# main.net
KiCad netlist of a schematic drawn in EAGLE
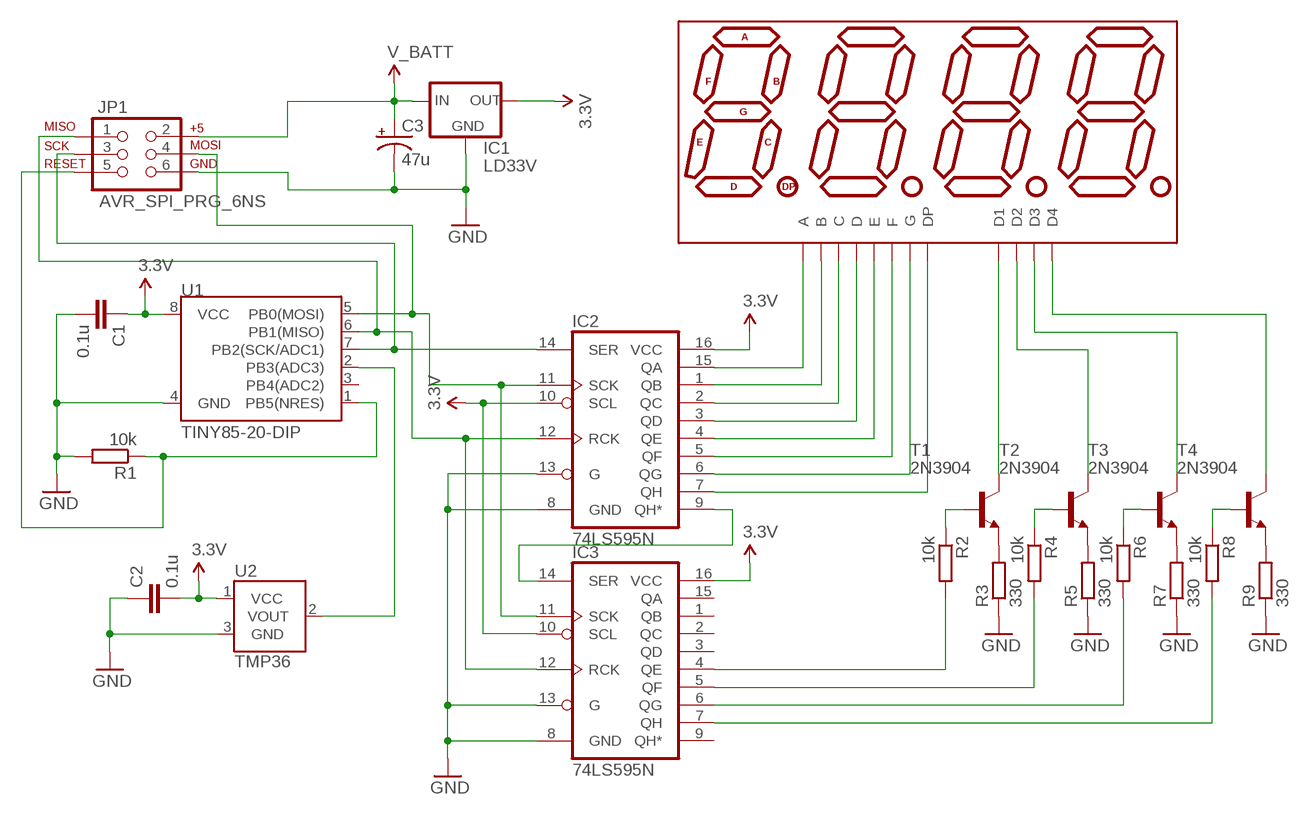
[diagram p0: schematic, sheet 1]

(export (version "E")
  (design (tool "Eeschema 10.0.6"))
  (components
    (comp (ref "C1")
      (value "0.1u")
      (footprint "eagle-import:C025-025X050")
      (libsource (lib "eagle-import") (part "C-EU025-025X050"))
    )
    (comp (ref "C2")
      (value "0.1u")
      (footprint "eagle-import:C025-025X050")
      (libsource (lib "eagle-import") (part "C-EU025-025X050"))
    )
    (comp (ref "C3")
      (value "47u")
      (footprint "eagle-import:CPOL-RADIAL-10UF-25V")
      (libsource (lib "eagle-import") (part "CAP_POLPTH2"))
    )
    (comp (ref "DISP1")
      (value "7-SEGMENT-4DIGIT-COUNTER-HP-BUBBLE")
      (footprint "eagle-import:DIL12")
      (libsource (lib "eagle-import") (part "7-SEGMENT-4DIGIT-COUNTER-HP-BUBBLE"))
    )
    (comp (ref "IC1")
      (value "LD33V")
      (footprint "eagle-import:78XXL")
      (libsource (lib "eagle-import") (part "78XXL"))
    )
    (comp (ref "IC2")
      (value "74LS595N")
      (footprint "eagle-import:DIL16")
      (libsource (lib "eagle-import") (part "74595NLS"))
    )
    (comp (ref "IC3")
      (value "74LS595N")
      (footprint "eagle-import:DIL16")
      (libsource (lib "eagle-import") (part "74595NLS"))
    )
    (comp (ref "JP1")
      (value "AVR_SPI_PRG_6NS")
      (footprint "eagle-import:2X3-NS")
      (libsource (lib "eagle-import") (part "AVR_SPI_PRG_6NS"))
    )
    (comp (ref "R1")
      (value "10k")
      (footprint "eagle-import:0204_7")
      (libsource (lib "eagle-import") (part "R-EU_0204/7"))
    )
    (comp (ref "R2")
      (value "10k")
      (footprint "eagle-import:0204V")
      (libsource (lib "eagle-import") (part "R-EU_0204/2V"))
    )
    (comp (ref "R3")
      (value "330")
      (footprint "eagle-import:0204V")
      (libsource (lib "eagle-import") (part "R-EU_0204/2V"))
    )
    (comp (ref "R4")
      (value "10k")
      (footprint "eagle-import:0204V")
      (libsource (lib "eagle-import") (part "R-EU_0204/2V"))
    )
    (comp (ref "R5")
      (value "330")
      (footprint "eagle-import:0204V")
      (libsource (lib "eagle-import") (part "R-EU_0204/2V"))
    )
    (comp (ref "R6")
      (value "10k")
      (footprint "eagle-import:0204V")
      (libsource (lib "eagle-import") (part "R-EU_0204/2V"))
    )
    (comp (ref "R7")
      (value "330")
      (footprint "eagle-import:0204V")
      (libsource (lib "eagle-import") (part "R-EU_0204/2V"))
    )
    (comp (ref "R8")
      (value "10k")
      (footprint "eagle-import:0204V")
      (libsource (lib "eagle-import") (part "R-EU_0204/2V"))
    )
    (comp (ref "R9")
      (value "330")
      (footprint "eagle-import:0204V")
      (libsource (lib "eagle-import") (part "R-EU_0204/2V"))
    )
    (comp (ref "T1")
      (value "2N3904")
      (footprint "eagle-import:TO92")
      (libsource (lib "eagle-import") (part "2N3904"))
    )
    (comp (ref "T2")
      (value "2N3904")
      (footprint "eagle-import:TO92")
      (libsource (lib "eagle-import") (part "2N3904"))
    )
    (comp (ref "T3")
      (value "2N3904")
      (footprint "eagle-import:TO92")
      (libsource (lib "eagle-import") (part "2N3904"))
    )
    (comp (ref "T4")
      (value "2N3904")
      (footprint "eagle-import:TO92")
      (libsource (lib "eagle-import") (part "2N3904"))
    )
    (comp (ref "U1")
      (value "TINY85-20-DIP")
      (footprint "eagle-import:DIP08")
      (libsource (lib "eagle-import") (part "ATTINY45TINY85-20-DIP"))
    )
    (comp (ref "U2")
      (value "TMP36")
      (footprint "eagle-import:TO-92")
      (libsource (lib "eagle-import") (part "TMP36GT9"))
    )
  )
  (nets
    (net (code "1") (name "3.3V") (class "Default")
      (node (ref "C1") (pin "1") (pinfunction "1_1") (pintype "passive"))
      (node (ref "C2") (pin "2") (pinfunction "2_2") (pintype "passive"))
      (node (ref "IC1") (pin "OUT") (pinfunction "OUT_OUT") (pintype "passive"))
      (node (ref "IC2") (pin "10") (pinfunction "SCL_10") (pintype "input"))
      (node (ref "IC2") (pin "16") (pinfunction "VCC_16") (pintype "power_in"))
      (node (ref "IC3") (pin "10") (pinfunction "SCL_10") (pintype "input"))
      (node (ref "IC3") (pin "16") (pinfunction "VCC_16") (pintype "power_in"))
      (node (ref "U1") (pin "8") (pinfunction "VCC_8") (pintype "bidirectional"))
      (node (ref "U2") (pin "1") (pinfunction "VCC_1") (pintype "bidirectional"))
    )
    (net (code "2") (name "GND") (class "Default")
      (node (ref "C1") (pin "2") (pinfunction "2_2") (pintype "passive"))
      (node (ref "C2") (pin "1") (pinfunction "1_1") (pintype "passive"))
      (node (ref "C3") (pin "2") (pinfunction "-_2") (pintype "passive"))
      (node (ref "IC1") (pin "GND") (pinfunction "GND_GND") (pintype "input"))
      (node (ref "IC2") (pin "13") (pinfunction "G_13") (pintype "input"))
      (node (ref "IC2") (pin "8") (pinfunction "GND_8") (pintype "power_in"))
      (node (ref "IC3") (pin "13") (pinfunction "G_13") (pintype "input"))
      (node (ref "IC3") (pin "8") (pinfunction "GND_8") (pintype "power_in"))
      (node (ref "JP1") (pin "6") (pinfunction "6_6") (pintype "passive"))
      (node (ref "R1") (pin "2") (pinfunction "2_2") (pintype "passive"))
      (node (ref "R3") (pin "1") (pinfunction "1_1") (pintype "passive"))
      (node (ref "R5") (pin "1") (pinfunction "1_1") (pintype "passive"))
      (node (ref "R7") (pin "1") (pinfunction "1_1") (pintype "passive"))
      (node (ref "R9") (pin "1") (pinfunction "1_1") (pintype "passive"))
      (node (ref "U1") (pin "4") (pinfunction "GND_4") (pintype "bidirectional"))
      (node (ref "U2") (pin "3") (pinfunction "GND_3") (pintype "bidirectional"))
    )
    (net (code "3") (name "Net-(DISP1-A)") (class "Default")
      (node (ref "DISP1") (pin "12") (pinfunction "A_12") (pintype "bidirectional"))
      (node (ref "IC2") (pin "15") (pinfunction "QA_15") (pintype "tri_state"))
    )
    (net (code "4") (name "Net-(DISP1-B)") (class "Default")
      (node (ref "DISP1") (pin "11") (pinfunction "B_11") (pintype "bidirectional"))
      (node (ref "IC2") (pin "1") (pinfunction "QB_1") (pintype "tri_state"))
    )
    (net (code "5") (name "Net-(DISP1-C)") (class "Default")
      (node (ref "DISP1") (pin "3") (pinfunction "C_3") (pintype "bidirectional"))
      (node (ref "IC2") (pin "2") (pinfunction "QC_2") (pintype "tri_state"))
    )
    (net (code "6") (name "Net-(DISP1-D)") (class "Default")
      (node (ref "DISP1") (pin "8") (pinfunction "D_8") (pintype "bidirectional"))
      (node (ref "IC2") (pin "3") (pinfunction "QD_3") (pintype "tri_state"))
    )
    (net (code "7") (name "Net-(DISP1-D1)") (class "Default")
      (node (ref "DISP1") (pin "1") (pinfunction "D1_1") (pintype "bidirectional"))
      (node (ref "T1") (pin "1") (pinfunction "C_1") (pintype "passive"))
    )
    (net (code "8") (name "Net-(DISP1-D2)") (class "Default")
      (node (ref "DISP1") (pin "10") (pinfunction "D2_10") (pintype "bidirectional"))
      (node (ref "T2") (pin "1") (pinfunction "C_1") (pintype "passive"))
    )
    (net (code "9") (name "Net-(DISP1-D3)") (class "Default")
      (node (ref "DISP1") (pin "4") (pinfunction "D3_4") (pintype "bidirectional"))
      (node (ref "T3") (pin "1") (pinfunction "C_1") (pintype "passive"))
    )
    (net (code "10") (name "Net-(DISP1-D4)") (class "Default")
      (node (ref "DISP1") (pin "6") (pinfunction "D4_6") (pintype "bidirectional"))
      (node (ref "T4") (pin "1") (pinfunction "C_1") (pintype "passive"))
    )
    (net (code "11") (name "Net-(DISP1-DP)") (class "Default")
      (node (ref "DISP1") (pin "5") (pinfunction "DP_5") (pintype "bidirectional"))
      (node (ref "IC2") (pin "7") (pinfunction "QH_7") (pintype "tri_state"))
    )
    (net (code "12") (name "Net-(DISP1-E)") (class "Default")
      (node (ref "DISP1") (pin "2") (pinfunction "E_2") (pintype "bidirectional"))
      (node (ref "IC2") (pin "4") (pinfunction "QE_4") (pintype "tri_state"))
    )
    (net (code "13") (name "Net-(DISP1-F)") (class "Default")
      (node (ref "DISP1") (pin "9") (pinfunction "F_9") (pintype "bidirectional"))
      (node (ref "IC2") (pin "5") (pinfunction "QF_5") (pintype "tri_state"))
    )
    (net (code "14") (name "Net-(DISP1-G)") (class "Default")
      (node (ref "DISP1") (pin "7") (pinfunction "G_7") (pintype "bidirectional"))
      (node (ref "IC2") (pin "6") (pinfunction "QG_6") (pintype "tri_state"))
    )
    (net (code "15") (name "Net-(IC2-QH*)") (class "Default")
      (node (ref "IC2") (pin "9") (pinfunction "QH*_9") (pintype "tri_state"))
      (node (ref "IC3") (pin "14") (pinfunction "SER_14") (pintype "input"))
    )
    (net (code "16") (name "Net-(IC2-RCK)") (class "Default")
      (node (ref "IC2") (pin "12") (pinfunction "RCK_12") (pintype "input"))
      (node (ref "IC3") (pin "12") (pinfunction "RCK_12") (pintype "input"))
      (node (ref "JP1") (pin "1") (pinfunction "1_1") (pintype "passive"))
      (node (ref "U1") (pin "6") (pinfunction "PB1(MISO)_6") (pintype "bidirectional"))
    )
    (net (code "17") (name "Net-(IC2-SCK)") (class "Default")
      (node (ref "IC2") (pin "11") (pinfunction "SCK_11") (pintype "input"))
      (node (ref "IC3") (pin "11") (pinfunction "SCK_11") (pintype "input"))
      (node (ref "JP1") (pin "4") (pinfunction "4_4") (pintype "passive"))
      (node (ref "U1") (pin "5") (pinfunction "PB0(MOSI)_5") (pintype "bidirectional"))
    )
    (net (code "18") (name "Net-(IC2-SER)") (class "Default")
      (node (ref "IC2") (pin "14") (pinfunction "SER_14") (pintype "input"))
      (node (ref "JP1") (pin "3") (pinfunction "3_3") (pintype "passive"))
      (node (ref "U1") (pin "7") (pinfunction "PB2(SCK/ADC1)_7") (pintype "bidirectional"))
    )
    (net (code "19") (name "Net-(IC3-QE)") (class "Default")
      (node (ref "IC3") (pin "4") (pinfunction "QE_4") (pintype "tri_state"))
      (node (ref "R2") (pin "2") (pinfunction "2_2") (pintype "passive"))
    )
    (net (code "20") (name "Net-(IC3-QF)") (class "Default")
      (node (ref "IC3") (pin "5") (pinfunction "QF_5") (pintype "tri_state"))
      (node (ref "R4") (pin "2") (pinfunction "2_2") (pintype "passive"))
    )
    (net (code "21") (name "Net-(IC3-QG)") (class "Default")
      (node (ref "IC3") (pin "6") (pinfunction "QG_6") (pintype "tri_state"))
      (node (ref "R6") (pin "2") (pinfunction "2_2") (pintype "passive"))
    )
    (net (code "22") (name "Net-(IC3-QH)") (class "Default")
      (node (ref "IC3") (pin "7") (pinfunction "QH_7") (pintype "tri_state"))
      (node (ref "R8") (pin "2") (pinfunction "2_2") (pintype "passive"))
    )
    (net (code "23") (name "Net-(T1-B)") (class "Default")
      (node (ref "R2") (pin "1") (pinfunction "1_1") (pintype "passive"))
      (node (ref "T1") (pin "2") (pinfunction "B_2") (pintype "passive"))
    )
    (net (code "24") (name "Net-(T1-E)") (class "Default")
      (node (ref "R3") (pin "2") (pinfunction "2_2") (pintype "passive"))
      (node (ref "T1") (pin "3") (pinfunction "E_3") (pintype "passive"))
    )
    (net (code "25") (name "Net-(T2-B)") (class "Default")
      (node (ref "R4") (pin "1") (pinfunction "1_1") (pintype "passive"))
      (node (ref "T2") (pin "2") (pinfunction "B_2") (pintype "passive"))
    )
    (net (code "26") (name "Net-(T2-E)") (class "Default")
      (node (ref "R5") (pin "2") (pinfunction "2_2") (pintype "passive"))
      (node (ref "T2") (pin "3") (pinfunction "E_3") (pintype "passive"))
    )
    (net (code "27") (name "Net-(T3-B)") (class "Default")
      (node (ref "R6") (pin "1") (pinfunction "1_1") (pintype "passive"))
      (node (ref "T3") (pin "2") (pinfunction "B_2") (pintype "passive"))
    )
    (net (code "28") (name "Net-(T3-E)") (class "Default")
      (node (ref "R7") (pin "2") (pinfunction "2_2") (pintype "passive"))
      (node (ref "T3") (pin "3") (pinfunction "E_3") (pintype "passive"))
    )
    (net (code "29") (name "Net-(T4-B)") (class "Default")
      (node (ref "R8") (pin "1") (pinfunction "1_1") (pintype "passive"))
      (node (ref "T4") (pin "2") (pinfunction "B_2") (pintype "passive"))
    )
    (net (code "30") (name "Net-(T4-E)") (class "Default")
      (node (ref "R9") (pin "2") (pinfunction "2_2") (pintype "passive"))
      (node (ref "T4") (pin "3") (pinfunction "E_3") (pintype "passive"))
    )
    (net (code "31") (name "Net-(U1-PB3(ADC3))") (class "Default")
      (node (ref "U1") (pin "2") (pinfunction "PB3(ADC3)_2") (pintype "bidirectional"))
      (node (ref "U2") (pin "2") (pinfunction "VOUT_2") (pintype "bidirectional"))
    )
    (net (code "32") (name "Net-(U1-PB5(NRES))") (class "Default")
      (node (ref "JP1") (pin "5") (pinfunction "5_5") (pintype "passive"))
      (node (ref "R1") (pin "1") (pinfunction "1_1") (pintype "passive"))
      (node (ref "U1") (pin "1") (pinfunction "PB5(NRES)_1") (pintype "bidirectional"))
    )
    (net (code "33") (name "V_BATT") (class "Default")
      (node (ref "C3") (pin "1") (pinfunction "+_1") (pintype "passive"))
      (node (ref "IC1") (pin "IN") (pinfunction "IN_IN") (pintype "input"))
      (node (ref "JP1") (pin "2") (pinfunction "2_2") (pintype "passive"))
    )
    (net (code "34") (name "unconnected-(IC3-QA-Pad15)") (class "Default")
      (node (ref "IC3") (pin "15") (pinfunction "QA_15") (pintype "tri_state"))
    )
    (net (code "35") (name "unconnected-(IC3-QB-Pad1)") (class "Default")
      (node (ref "IC3") (pin "1") (pinfunction "QB_1") (pintype "tri_state"))
    )
    (net (code "36") (name "unconnected-(IC3-QC-Pad2)") (class "Default")
      (node (ref "IC3") (pin "2") (pinfunction "QC_2") (pintype "tri_state"))
    )
    (net (code "37") (name "unconnected-(IC3-QD-Pad3)") (class "Default")
      (node (ref "IC3") (pin "3") (pinfunction "QD_3") (pintype "tri_state"))
    )
    (net (code "38") (name "unconnected-(IC3-QH*-Pad9)") (class "Default")
      (node (ref "IC3") (pin "9") (pinfunction "QH*_9") (pintype "tri_state"))
    )
    (net (code "39") (name "unconnected-(U1-PB4(ADC2)-Pad3)") (class "Default")
      (node (ref "U1") (pin "3") (pinfunction "PB4(ADC2)_3") (pintype "bidirectional"))
    )
  )
)
